# AP6212WIFI.net
KiCad netlist of a schematic drawn in Altium Designer
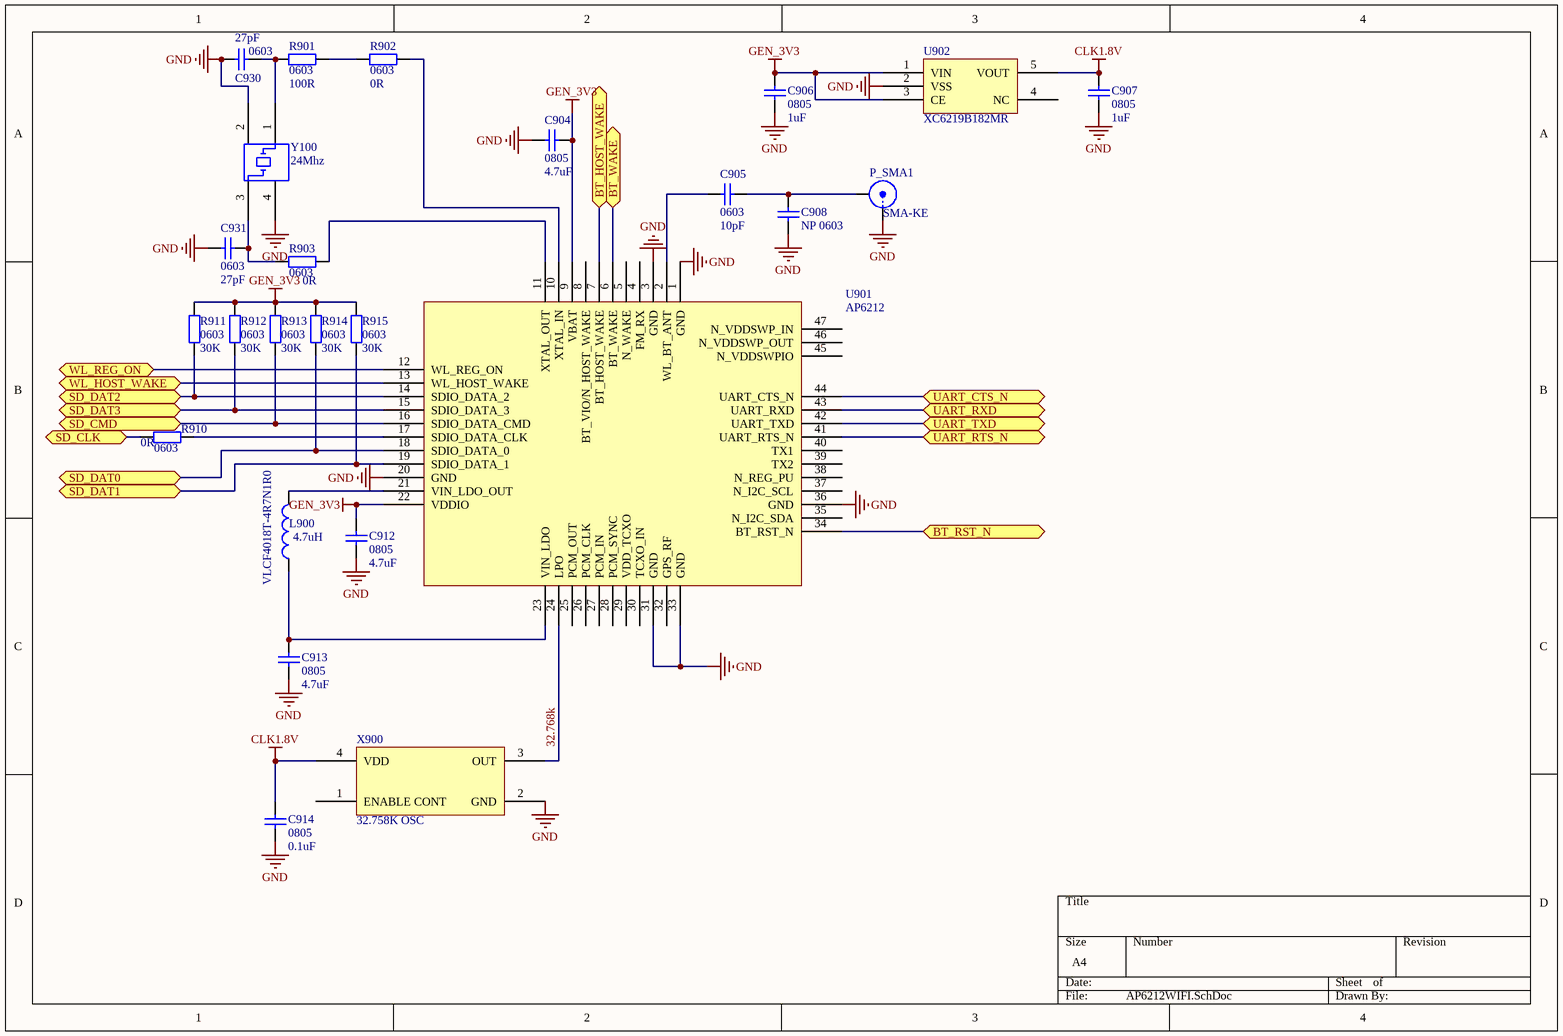
[diagram p0: AP6212WIFI.SchDoc]

(export (version "E")
  (design (tool "Eeschema 10.0.6"))
  (components
    (comp (ref "C904")
      (value "0805")
      (footprint "0805")
      (description "Capacitor")
      (fields (field (name "ALTIUM_VALUE") "4.7uF") (field (name "PUBLISHER") "Altium Limited"))
      (libsource (lib "Miscellaneous Devices") (part "Cap"))
    )
    (comp (ref "C905")
      (value "0603")
      (footprint "0603")
      (description "Capacitor")
      (fields (field (name "ALTIUM_VALUE") "10pF") (field (name "PUBLISHER") "Altium Limited"))
      (libsource (lib "Miscellaneous Devices") (part "Cap"))
    )
    (comp (ref "C906")
      (value "0805")
      (footprint "0805")
      (description "Capacitor")
      (fields (field (name "ALTIUM_VALUE") "1uF") (field (name "PUBLISHER") "Altium Limited"))
      (libsource (lib "Miscellaneous Devices") (part "Cap"))
    )
    (comp (ref "C907")
      (value "0805")
      (footprint "0805")
      (description "Capacitor")
      (fields (field (name "ALTIUM_VALUE") "1uF") (field (name "PUBLISHER") "Altium Limited"))
      (libsource (lib "Miscellaneous Devices") (part "Cap"))
    )
    (comp (ref "C908")
      (value "NP 0603")
      (footprint "0603")
      (description "Capacitor")
      (fields (field (name "PUBLISHER") "Altium Limited"))
      (libsource (lib "Miscellaneous Devices") (part "Cap"))
    )
    (comp (ref "C912")
      (value "0805")
      (footprint "0805")
      (description "Capacitor")
      (fields (field (name "ALTIUM_VALUE") "4.7uF") (field (name "PUBLISHER") "Altium Limited"))
      (libsource (lib "Miscellaneous Devices") (part "Cap"))
    )
    (comp (ref "C913")
      (value "0805")
      (footprint "0805")
      (description "Capacitor")
      (fields (field (name "ALTIUM_VALUE") "4.7uF") (field (name "PUBLISHER") "Altium Limited"))
      (libsource (lib "Miscellaneous Devices") (part "Cap"))
    )
    (comp (ref "C914")
      (value "0805")
      (footprint "0805")
      (description "Capacitor")
      (fields (field (name "ALTIUM_VALUE") "0.1uF") (field (name "PUBLISHER") "Altium Limited"))
      (libsource (lib "Miscellaneous Devices") (part "Cap"))
    )
    (comp (ref "C930")
      (value "0603")
      (footprint "0603")
      (description "Capacitor")
      (fields (field (name "ALTIUM_VALUE") "27pF") (field (name "PUBLISHER") "Altium Limited"))
      (libsource (lib "Miscellaneous Devices") (part "Cap"))
    )
    (comp (ref "C931")
      (value "0603")
      (footprint "0603")
      (description "Capacitor")
      (fields (field (name "ALTIUM_VALUE") "27pF") (field (name "PUBLISHER") "Altium Limited"))
      (libsource (lib "Miscellaneous Devices") (part "Cap"))
    )
    (comp (ref "L900")
      (value "VLCF4018T-4R7N1R0")
      (footprint "VLCF4018-2-inductor")
      (description "Inductor")
      (fields (field (name "ALTIUM_VALUE") "4.7uH") (field (name "PUBLISHER") "Altium Limited"))
      (libsource (lib "Miscellaneous Devices") (part "Inductor"))
    )
    (comp (ref "P_SMA1")
      (value "SMA-KE")
      (footprint "2.4Gantenna-IPEX")
      (description "BNC Elbow Connector")
      (fields (field (name "PUBLISHER") "Altium Limited"))
      (libsource (lib "Miscellaneous Connectors") (part "BNC"))
    )
    (comp (ref "R901")
      (value "0603")
      (footprint "0603")
      (description "Resistor")
      (fields (field (name "ALTIUM_VALUE") "100R") (field (name "PUBLISHER") "Altium Limited"))
      (libsource (lib "") (part "Res2_1"))
    )
    (comp (ref "R902")
      (value "0603")
      (footprint "0603")
      (description "Resistor")
      (fields (field (name "ALTIUM_VALUE") "0R") (field (name "PUBLISHER") "Altium Limited"))
      (libsource (lib "") (part "Res2_2"))
    )
    (comp (ref "R903")
      (value "0603")
      (footprint "0603")
      (description "Resistor")
      (fields (field (name "ALTIUM_VALUE") "0R") (field (name "PUBLISHER") "Altium Limited"))
      (libsource (lib "") (part "Res2_2"))
    )
    (comp (ref "R910")
      (value "0603")
      (footprint "0603")
      (description "Resistor")
      (fields (field (name "ALTIUM_VALUE") "0R") (field (name "PUBLISHER") "Altium Limited"))
      (libsource (lib "") (part "Res2_2"))
    )
    (comp (ref "R911")
      (value "0603")
      (footprint "0603")
      (description "Resistor")
      (fields (field (name "ALTIUM_VALUE") "30K") (field (name "PUBLISHER") "Altium Limited"))
      (libsource (lib "Miscellaneous Devices") (part "Res2"))
    )
    (comp (ref "R912")
      (value "0603")
      (footprint "0603")
      (description "Resistor")
      (fields (field (name "ALTIUM_VALUE") "30K") (field (name "PUBLISHER") "Altium Limited"))
      (libsource (lib "Miscellaneous Devices") (part "Res2"))
    )
    (comp (ref "R913")
      (value "0603")
      (footprint "0603")
      (description "Resistor")
      (fields (field (name "ALTIUM_VALUE") "30K") (field (name "PUBLISHER") "Altium Limited"))
      (libsource (lib "Miscellaneous Devices") (part "Res2"))
    )
    (comp (ref "R914")
      (value "0603")
      (footprint "0603")
      (description "Resistor")
      (fields (field (name "ALTIUM_VALUE") "30K") (field (name "PUBLISHER") "Altium Limited"))
      (libsource (lib "Miscellaneous Devices") (part "Res2"))
    )
    (comp (ref "R915")
      (value "0603")
      (footprint "0603")
      (description "Resistor")
      (fields (field (name "ALTIUM_VALUE") "30K") (field (name "PUBLISHER") "Altium Limited"))
      (libsource (lib "Miscellaneous Devices") (part "Res2"))
    )
    (comp (ref "U901") (value "AP6212") (footprint "AP6212-LCC44") (libsource (lib "IMX6DL") (part "AP6212")))
    (comp (ref "U902")
      (value "XC6219B182MR")
      (footprint "XC6219B182MR-SOT-25")
      (libsource (lib "IMX6DL") (part "XC6219B182MR"))
    )
    (comp (ref "X900")
      (value "32.758K OSC")
      (footprint "32.768K OSC")
      (libsource (lib "IMX6DL") (part "32.758K OSC"))
    )
    (comp (ref "Y100")
      (value "24Mhz")
      (footprint "XTL571300LLI24.000-10TR")
      (libsource (lib "IMX6DL") (part "XTAL"))
    )
  )
  (nets
    (net (code "1") (name "/32.768k") (class "Default")
      (node (ref "U901") (pin "24") (pinfunction "LPO_24") (pintype "passive"))
      (node (ref "X900") (pin "3") (pinfunction "OUT_3") (pintype "passive"))
    )
    (net (code "2") (name "/BT_HOST_WAKE") (class "Default")
      (node (ref "U901") (pin "7") (pinfunction "BT_HOST_WAKE_7") (pintype "passive"))
    )
    (net (code "3") (name "/BT_RST_N") (class "Default")
      (node (ref "U901") (pin "34") (pinfunction "BT_RST_N_34") (pintype "passive"))
    )
    (net (code "4") (name "/BT_WAKE") (class "Default")
      (node (ref "U901") (pin "6") (pinfunction "BT_WAKE_6") (pintype "passive"))
    )
    (net (code "5") (name "/SD_CLK") (class "Default")
      (node (ref "R910") (pin "2") (pinfunction "2_2") (pintype "passive"))
    )
    (net (code "6") (name "/SD_CMD") (class "Default")
      (node (ref "R913") (pin "1") (pinfunction "1_1") (pintype "passive"))
      (node (ref "U901") (pin "16") (pinfunction "SDIO_DATA_CMD_16") (pintype "passive"))
    )
    (net (code "7") (name "/SD_DAT0") (class "Default")
      (node (ref "R914") (pin "1") (pinfunction "1_1") (pintype "passive"))
      (node (ref "U901") (pin "18") (pinfunction "SDIO_DATA_0_18") (pintype "passive"))
    )
    (net (code "8") (name "/SD_DAT1") (class "Default")
      (node (ref "R915") (pin "1") (pinfunction "1_1") (pintype "passive"))
      (node (ref "U901") (pin "19") (pinfunction "SDIO_DATA_1_19") (pintype "passive"))
    )
    (net (code "9") (name "/SD_DAT2") (class "Default")
      (node (ref "R911") (pin "1") (pinfunction "1_1") (pintype "passive"))
      (node (ref "U901") (pin "14") (pinfunction "SDIO_DATA_2_14") (pintype "passive"))
    )
    (net (code "10") (name "/SD_DAT3") (class "Default")
      (node (ref "R912") (pin "1") (pinfunction "1_1") (pintype "passive"))
      (node (ref "U901") (pin "15") (pinfunction "SDIO_DATA_3_15") (pintype "passive"))
    )
    (net (code "11") (name "/UART_CTS_N") (class "Default")
      (node (ref "U901") (pin "44") (pinfunction "UART_CTS_N_44") (pintype "passive"))
    )
    (net (code "12") (name "/UART_RTS_N") (class "Default")
      (node (ref "U901") (pin "41") (pinfunction "UART_RTS_N_41") (pintype "passive"))
    )
    (net (code "13") (name "/UART_RXD") (class "Default")
      (node (ref "U901") (pin "43") (pinfunction "UART_RXD_43") (pintype "passive"))
    )
    (net (code "14") (name "/UART_TXD") (class "Default")
      (node (ref "U901") (pin "42") (pinfunction "UART_TXD_42") (pintype "passive"))
    )
    (net (code "15") (name "/WL_HOST_WAKE") (class "Default")
      (node (ref "U901") (pin "13") (pinfunction "WL_HOST_WAKE_13") (pintype "passive"))
    )
    (net (code "16") (name "/WL_REG_ON") (class "Default")
      (node (ref "U901") (pin "12") (pinfunction "WL_REG_ON_12") (pintype "passive"))
    )
    (net (code "17") (name "CLK1.8V") (class "Default")
      (node (ref "C907") (pin "2") (pinfunction "2_2") (pintype "passive"))
      (node (ref "C914") (pin "2") (pinfunction "2_2") (pintype "passive"))
      (node (ref "U902") (pin "5") (pinfunction "VOUT_5") (pintype "passive"))
      (node (ref "X900") (pin "4") (pinfunction "VDD_4") (pintype "passive"))
    )
    (net (code "18") (name "GEN_3V3") (class "Default")
      (node (ref "C904") (pin "1") (pinfunction "1_1") (pintype "passive"))
      (node (ref "C906") (pin "2") (pinfunction "2_2") (pintype "passive"))
      (node (ref "C912") (pin "2") (pinfunction "2_2") (pintype "passive"))
      (node (ref "R911") (pin "2") (pinfunction "2_2") (pintype "passive"))
      (node (ref "R912") (pin "2") (pinfunction "2_2") (pintype "passive"))
      (node (ref "R913") (pin "2") (pinfunction "2_2") (pintype "passive"))
      (node (ref "R914") (pin "2") (pinfunction "2_2") (pintype "passive"))
      (node (ref "R915") (pin "2") (pinfunction "2_2") (pintype "passive"))
      (node (ref "U901") (pin "22") (pinfunction "VDDIO_22") (pintype "passive"))
      (node (ref "U901") (pin "9") (pinfunction "VBAT_9") (pintype "passive"))
      (node (ref "U902") (pin "1") (pinfunction "VIN_1") (pintype "passive"))
      (node (ref "U902") (pin "3") (pinfunction "CE_3") (pintype "passive"))
    )
    (net (code "19") (name "GND") (class "Default")
      (node (ref "C904") (pin "2") (pinfunction "2_2") (pintype "passive"))
      (node (ref "C906") (pin "1") (pinfunction "1_1") (pintype "passive"))
      (node (ref "C907") (pin "1") (pinfunction "1_1") (pintype "passive"))
      (node (ref "C908") (pin "2") (pinfunction "2_2") (pintype "passive"))
      (node (ref "C912") (pin "1") (pinfunction "1_1") (pintype "passive"))
      (node (ref "C913") (pin "1") (pinfunction "1_1") (pintype "passive"))
      (node (ref "C914") (pin "1") (pinfunction "1_1") (pintype "passive"))
      (node (ref "C930") (pin "1") (pinfunction "1_1") (pintype "passive"))
      (node (ref "C931") (pin "1") (pinfunction "1_1") (pintype "passive"))
      (node (ref "P_SMA1") (pin "1") (pinfunction "X_1") (pintype "passive"))
      (node (ref "U901") (pin "1") (pinfunction "GND_1") (pintype "passive"))
      (node (ref "U901") (pin "20") (pinfunction "GND_20") (pintype "passive"))
      (node (ref "U901") (pin "3") (pinfunction "GND_3") (pintype "passive"))
      (node (ref "U901") (pin "31") (pinfunction "GND_31") (pintype "passive"))
      (node (ref "U901") (pin "33") (pinfunction "GND_33") (pintype "passive"))
      (node (ref "U901") (pin "36") (pinfunction "GND_36") (pintype "passive"))
      (node (ref "U902") (pin "2") (pinfunction "VSS_2") (pintype "passive"))
      (node (ref "X900") (pin "2") (pinfunction "GND_2") (pintype "passive"))
      (node (ref "Y100") (pin "2") (pinfunction "58_2") (pintype "passive"))
      (node (ref "Y100") (pin "4") (pinfunction "60_4") (pintype "passive"))
    )
    (net (code "20") (name "Net-(P_SMA1-Y)") (class "Default")
      (node (ref "C905") (pin "2") (pinfunction "2_2") (pintype "passive"))
      (node (ref "C908") (pin "1") (pinfunction "1_1") (pintype "passive"))
      (node (ref "P_SMA1") (pin "2") (pinfunction "Y_2") (pintype "passive"))
    )
    (net (code "21") (name "Net-(R901-Pad2)") (class "Default")
      (node (ref "R901") (pin "2") (pinfunction "2_2") (pintype "passive"))
      (node (ref "R902") (pin "2") (pinfunction "2_2") (pintype "passive"))
    )
    (net (code "22") (name "Net-(U901-SDIO_DATA_CLK)") (class "Default")
      (node (ref "R910") (pin "1") (pinfunction "1_1") (pintype "passive"))
      (node (ref "U901") (pin "17") (pinfunction "SDIO_DATA_CLK_17") (pintype "passive"))
    )
    (net (code "23") (name "Net-(U901-VIN_LDO)") (class "Default")
      (node (ref "C913") (pin "2") (pinfunction "2_2") (pintype "passive"))
      (node (ref "L900") (pin "1") (pinfunction "1_1") (pintype "passive"))
      (node (ref "U901") (pin "23") (pinfunction "VIN_LDO_23") (pintype "passive"))
    )
    (net (code "24") (name "Net-(U901-VIN_LDO_OUT)") (class "Default")
      (node (ref "L900") (pin "2") (pinfunction "2_2") (pintype "passive"))
      (node (ref "U901") (pin "21") (pinfunction "VIN_LDO_OUT_21") (pintype "passive"))
    )
    (net (code "25") (name "Net-(U901-WL_BT_ANT)") (class "Default")
      (node (ref "C905") (pin "1") (pinfunction "1_1") (pintype "passive"))
      (node (ref "U901") (pin "2") (pinfunction "WL_BT_ANT_2") (pintype "passive"))
    )
    (net (code "26") (name "Net-(U901-XTAL_IN)") (class "Default")
      (node (ref "R902") (pin "1") (pinfunction "1_1") (pintype "passive"))
      (node (ref "U901") (pin "10") (pinfunction "XTAL_IN_10") (pintype "passive"))
    )
    (net (code "27") (name "Net-(U901-XTAL_OUT)") (class "Default")
      (node (ref "R903") (pin "1") (pinfunction "1_1") (pintype "passive"))
      (node (ref "U901") (pin "11") (pinfunction "XTAL_OUT_11") (pintype "passive"))
    )
    (net (code "28") (name "Net-(Y100-57)") (class "Default")
      (node (ref "C930") (pin "2") (pinfunction "2_2") (pintype "passive"))
      (node (ref "R901") (pin "1") (pinfunction "1_1") (pintype "passive"))
      (node (ref "Y100") (pin "1") (pinfunction "57_1") (pintype "passive"))
    )
    (net (code "29") (name "Net-(Y100-59)") (class "Default")
      (node (ref "C931") (pin "2") (pinfunction "2_2") (pintype "passive"))
      (node (ref "R903") (pin "2") (pinfunction "2_2") (pintype "passive"))
      (node (ref "Y100") (pin "3") (pinfunction "59_3") (pintype "passive"))
    )
    (net (code "30") (name "unconnected-(U901-BT_VIO{slash}N_HOST_WAKE-Pad8)") (class "Default")
      (node (ref "U901") (pin "8") (pinfunction "BT_VIO/N_HOST_WAKE_8") (pintype "passive"))
    )
    (net (code "31") (name "unconnected-(U901-FM_RX-Pad4)") (class "Default")
      (node (ref "U901") (pin "4") (pinfunction "FM_RX_4") (pintype "passive"))
    )
    (net (code "32") (name "unconnected-(U901-GPS_RF-Pad32)") (class "Default")
      (node (ref "U901") (pin "32") (pinfunction "GPS_RF_32") (pintype "passive"))
    )
    (net (code "33") (name "unconnected-(U901-N_I2C_SCL-Pad37)") (class "Default")
      (node (ref "U901") (pin "37") (pinfunction "N_I2C_SCL_37") (pintype "passive"))
    )
    (net (code "34") (name "unconnected-(U901-N_I2C_SDA-Pad35)") (class "Default")
      (node (ref "U901") (pin "35") (pinfunction "N_I2C_SDA_35") (pintype "passive"))
    )
    (net (code "35") (name "unconnected-(U901-N_REG_PU-Pad38)") (class "Default")
      (node (ref "U901") (pin "38") (pinfunction "N_REG_PU_38") (pintype "passive"))
    )
    (net (code "36") (name "unconnected-(U901-N_VDDSWPIO-Pad45)") (class "Default")
      (node (ref "U901") (pin "45") (pinfunction "N_VDDSWPIO_45") (pintype "passive"))
    )
    (net (code "37") (name "unconnected-(U901-N_VDDSWP_IN-Pad47)") (class "Default")
      (node (ref "U901") (pin "47") (pinfunction "N_VDDSWP_IN_47") (pintype "passive"))
    )
    (net (code "38") (name "unconnected-(U901-N_VDDSWP_OUT-Pad46)") (class "Default")
      (node (ref "U901") (pin "46") (pinfunction "N_VDDSWP_OUT_46") (pintype "passive"))
    )
    (net (code "39") (name "unconnected-(U901-N_WAKE-Pad5)") (class "Default")
      (node (ref "U901") (pin "5") (pinfunction "N_WAKE_5") (pintype "passive"))
    )
    (net (code "40") (name "unconnected-(U901-PCM_CLK-Pad26)") (class "Default")
      (node (ref "U901") (pin "26") (pinfunction "PCM_CLK_26") (pintype "passive"))
    )
    (net (code "41") (name "unconnected-(U901-PCM_IN-Pad27)") (class "Default")
      (node (ref "U901") (pin "27") (pinfunction "PCM_IN_27") (pintype "passive"))
    )
    (net (code "42") (name "unconnected-(U901-PCM_OUT-Pad25)") (class "Default")
      (node (ref "U901") (pin "25") (pinfunction "PCM_OUT_25") (pintype "passive"))
    )
    (net (code "43") (name "unconnected-(U901-PCM_SYNC-Pad28)") (class "Default")
      (node (ref "U901") (pin "28") (pinfunction "PCM_SYNC_28") (pintype "passive"))
    )
    (net (code "44") (name "unconnected-(U901-TCXO_IN-Pad30)") (class "Default")
      (node (ref "U901") (pin "30") (pinfunction "TCXO_IN_30") (pintype "passive"))
    )
    (net (code "45") (name "unconnected-(U901-TX1-Pad40)") (class "Default")
      (node (ref "U901") (pin "40") (pinfunction "TX1_40") (pintype "passive"))
    )
    (net (code "46") (name "unconnected-(U901-TX2-Pad39)") (class "Default")
      (node (ref "U901") (pin "39") (pinfunction "TX2_39") (pintype "passive"))
    )
    (net (code "47") (name "unconnected-(U901-VDD_TCXO-Pad29)") (class "Default")
      (node (ref "U901") (pin "29") (pinfunction "VDD_TCXO_29") (pintype "passive"))
    )
    (net (code "48") (name "unconnected-(U902-NC-Pad4)") (class "Default")
      (node (ref "U902") (pin "4") (pinfunction "NC_4") (pintype "passive"))
    )
    (net (code "49") (name "unconnected-(X900-ENABLE_CONT-Pad1)") (class "Default")
      (node (ref "X900") (pin "1") (pinfunction "ENABLE_CONT_1") (pintype "passive"))
    )
  )
)
